# MouseGoggles_EyeTrack_Hat-1-1.net
KiCad netlist of a schematic drawn in EAGLE
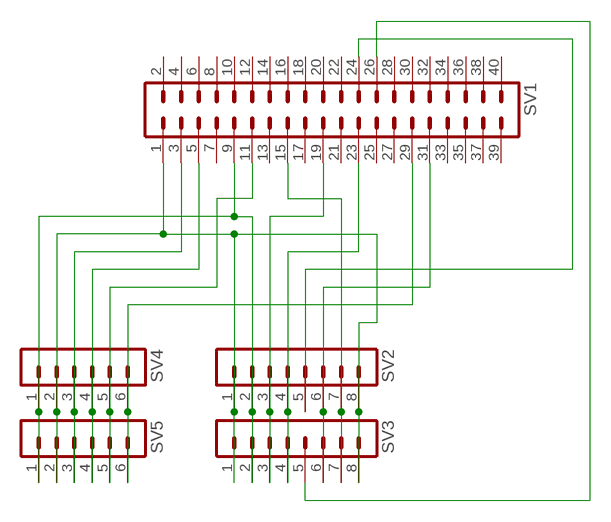
[diagram p0: schematic, sheet 1]

(export (version "E")
  (design (tool "Eeschema 10.0.6"))
  (components
    (comp (ref "SV1")
      (value "MA20-2")
      (footprint "eagle-import:MA20-2")
      (libsource (lib "eagle-import") (part "MA20-2"))
    )
    (comp (ref "SV2")
      (value "MA08-1")
      (footprint "eagle-import:MA08-1")
      (libsource (lib "eagle-import") (part "MA08-1"))
    )
    (comp (ref "SV3")
      (value "MA08-1")
      (footprint "eagle-import:MA08-1")
      (libsource (lib "eagle-import") (part "MA08-1"))
    )
    (comp (ref "SV4")
      (value "MA06-1")
      (footprint "eagle-import:MA06-1")
      (libsource (lib "eagle-import") (part "MA06-1"))
    )
    (comp (ref "SV5")
      (value "MA06-1")
      (footprint "eagle-import:MA06-1")
      (libsource (lib "eagle-import") (part "MA06-1"))
    )
  )
  (nets
    (net (code "1") (name "Net-(SV1-Pad1)") (class "Default")
      (node (ref "SV1") (pin "1") (pinfunction "1_1") (pintype "passive"))
      (node (ref "SV2") (pin "1") (pinfunction "1_1") (pintype "passive"))
      (node (ref "SV2") (pin "8") (pinfunction "8_8") (pintype "passive"))
      (node (ref "SV3") (pin "1") (pinfunction "1_1") (pintype "passive"))
      (node (ref "SV3") (pin "8") (pinfunction "8_8") (pintype "passive"))
      (node (ref "SV4") (pin "2") (pinfunction "2_2") (pintype "passive"))
      (node (ref "SV5") (pin "2") (pinfunction "2_2") (pintype "passive"))
    )
    (net (code "2") (name "Net-(SV1-Pad3)") (class "Default")
      (node (ref "SV1") (pin "3") (pinfunction "3_3") (pintype "passive"))
      (node (ref "SV4") (pin "3") (pinfunction "3_3") (pintype "passive"))
      (node (ref "SV5") (pin "3") (pinfunction "3_3") (pintype "passive"))
    )
    (net (code "3") (name "Net-(SV1-Pad5)") (class "Default")
      (node (ref "SV1") (pin "5") (pinfunction "5_5") (pintype "passive"))
      (node (ref "SV4") (pin "4") (pinfunction "4_4") (pintype "passive"))
      (node (ref "SV5") (pin "4") (pinfunction "4_4") (pintype "passive"))
    )
    (net (code "4") (name "Net-(SV1-Pad9)") (class "Default")
      (node (ref "SV1") (pin "9") (pinfunction "9_9") (pintype "passive"))
      (node (ref "SV2") (pin "2") (pinfunction "2_2") (pintype "passive"))
      (node (ref "SV3") (pin "2") (pinfunction "2_2") (pintype "passive"))
      (node (ref "SV4") (pin "1") (pinfunction "1_1") (pintype "passive"))
      (node (ref "SV5") (pin "1") (pinfunction "1_1") (pintype "passive"))
    )
    (net (code "5") (name "Net-(SV1-Pad11)") (class "Default")
      (node (ref "SV1") (pin "11") (pinfunction "11_11") (pintype "passive"))
      (node (ref "SV4") (pin "5") (pinfunction "5_5") (pintype "passive"))
      (node (ref "SV5") (pin "5") (pinfunction "5_5") (pintype "passive"))
    )
    (net (code "6") (name "Net-(SV1-Pad15)") (class "Default")
      (node (ref "SV1") (pin "15") (pinfunction "15_15") (pintype "passive"))
      (node (ref "SV2") (pin "7") (pinfunction "7_7") (pintype "passive"))
      (node (ref "SV3") (pin "7") (pinfunction "7_7") (pintype "passive"))
    )
    (net (code "7") (name "Net-(SV1-Pad19)") (class "Default")
      (node (ref "SV1") (pin "19") (pinfunction "19_19") (pintype "passive"))
      (node (ref "SV2") (pin "3") (pinfunction "3_3") (pintype "passive"))
      (node (ref "SV3") (pin "3") (pinfunction "3_3") (pintype "passive"))
    )
    (net (code "8") (name "Net-(SV1-Pad23)") (class "Default")
      (node (ref "SV1") (pin "23") (pinfunction "23_23") (pintype "passive"))
      (node (ref "SV2") (pin "4") (pinfunction "4_4") (pintype "passive"))
      (node (ref "SV3") (pin "4") (pinfunction "4_4") (pintype "passive"))
    )
    (net (code "9") (name "Net-(SV1-Pad24)") (class "Default")
      (node (ref "SV1") (pin "24") (pinfunction "24_24") (pintype "passive"))
      (node (ref "SV2") (pin "5") (pinfunction "5_5") (pintype "passive"))
    )
    (net (code "10") (name "Net-(SV1-Pad26)") (class "Default")
      (node (ref "SV1") (pin "26") (pinfunction "26_26") (pintype "passive"))
      (node (ref "SV3") (pin "5") (pinfunction "5_5") (pintype "passive"))
    )
    (net (code "11") (name "Net-(SV1-Pad29)") (class "Default")
      (node (ref "SV1") (pin "29") (pinfunction "29_29") (pintype "passive"))
      (node (ref "SV4") (pin "6") (pinfunction "6_6") (pintype "passive"))
      (node (ref "SV5") (pin "6") (pinfunction "6_6") (pintype "passive"))
    )
    (net (code "12") (name "Net-(SV1-Pad31)") (class "Default")
      (node (ref "SV1") (pin "31") (pinfunction "31_31") (pintype "passive"))
      (node (ref "SV2") (pin "6") (pinfunction "6_6") (pintype "passive"))
      (node (ref "SV3") (pin "6") (pinfunction "6_6") (pintype "passive"))
    )
    (net (code "13") (name "unconnected-(SV1-Pad2)") (class "Default")
      (node (ref "SV1") (pin "2") (pinfunction "2_2") (pintype "passive"))
    )
    (net (code "14") (name "unconnected-(SV1-Pad4)") (class "Default")
      (node (ref "SV1") (pin "4") (pinfunction "4_4") (pintype "passive"))
    )
    (net (code "15") (name "unconnected-(SV1-Pad6)") (class "Default")
      (node (ref "SV1") (pin "6") (pinfunction "6_6") (pintype "passive"))
    )
    (net (code "16") (name "unconnected-(SV1-Pad7)") (class "Default")
      (node (ref "SV1") (pin "7") (pinfunction "7_7") (pintype "passive"))
    )
    (net (code "17") (name "unconnected-(SV1-Pad8)") (class "Default")
      (node (ref "SV1") (pin "8") (pinfunction "8_8") (pintype "passive"))
    )
    (net (code "18") (name "unconnected-(SV1-Pad10)") (class "Default")
      (node (ref "SV1") (pin "10") (pinfunction "10_10") (pintype "passive"))
    )
    (net (code "19") (name "unconnected-(SV1-Pad12)") (class "Default")
      (node (ref "SV1") (pin "12") (pinfunction "12_12") (pintype "passive"))
    )
    (net (code "20") (name "unconnected-(SV1-Pad13)") (class "Default")
      (node (ref "SV1") (pin "13") (pinfunction "13_13") (pintype "passive"))
    )
    (net (code "21") (name "unconnected-(SV1-Pad14)") (class "Default")
      (node (ref "SV1") (pin "14") (pinfunction "14_14") (pintype "passive"))
    )
    (net (code "22") (name "unconnected-(SV1-Pad16)") (class "Default")
      (node (ref "SV1") (pin "16") (pinfunction "16_16") (pintype "passive"))
    )
    (net (code "23") (name "unconnected-(SV1-Pad17)") (class "Default")
      (node (ref "SV1") (pin "17") (pinfunction "17_17") (pintype "passive"))
    )
    (net (code "24") (name "unconnected-(SV1-Pad18)") (class "Default")
      (node (ref "SV1") (pin "18") (pinfunction "18_18") (pintype "passive"))
    )
    (net (code "25") (name "unconnected-(SV1-Pad20)") (class "Default")
      (node (ref "SV1") (pin "20") (pinfunction "20_20") (pintype "passive"))
    )
    (net (code "26") (name "unconnected-(SV1-Pad21)") (class "Default")
      (node (ref "SV1") (pin "21") (pinfunction "21_21") (pintype "passive"))
    )
    (net (code "27") (name "unconnected-(SV1-Pad22)") (class "Default")
      (node (ref "SV1") (pin "22") (pinfunction "22_22") (pintype "passive"))
    )
    (net (code "28") (name "unconnected-(SV1-Pad25)") (class "Default")
      (node (ref "SV1") (pin "25") (pinfunction "25_25") (pintype "passive"))
    )
    (net (code "29") (name "unconnected-(SV1-Pad27)") (class "Default")
      (node (ref "SV1") (pin "27") (pinfunction "27_27") (pintype "passive"))
    )
    (net (code "30") (name "unconnected-(SV1-Pad28)") (class "Default")
      (node (ref "SV1") (pin "28") (pinfunction "28_28") (pintype "passive"))
    )
    (net (code "31") (name "unconnected-(SV1-Pad30)") (class "Default")
      (node (ref "SV1") (pin "30") (pinfunction "30_30") (pintype "passive"))
    )
    (net (code "32") (name "unconnected-(SV1-Pad32)") (class "Default")
      (node (ref "SV1") (pin "32") (pinfunction "32_32") (pintype "passive"))
    )
    (net (code "33") (name "unconnected-(SV1-Pad33)") (class "Default")
      (node (ref "SV1") (pin "33") (pinfunction "33_33") (pintype "passive"))
    )
    (net (code "34") (name "unconnected-(SV1-Pad34)") (class "Default")
      (node (ref "SV1") (pin "34") (pinfunction "34_34") (pintype "passive"))
    )
    (net (code "35") (name "unconnected-(SV1-Pad35)") (class "Default")
      (node (ref "SV1") (pin "35") (pinfunction "35_35") (pintype "passive"))
    )
    (net (code "36") (name "unconnected-(SV1-Pad36)") (class "Default")
      (node (ref "SV1") (pin "36") (pinfunction "36_36") (pintype "passive"))
    )
    (net (code "37") (name "unconnected-(SV1-Pad37)") (class "Default")
      (node (ref "SV1") (pin "37") (pinfunction "37_37") (pintype "passive"))
    )
    (net (code "38") (name "unconnected-(SV1-Pad38)") (class "Default")
      (node (ref "SV1") (pin "38") (pinfunction "38_38") (pintype "passive"))
    )
    (net (code "39") (name "unconnected-(SV1-Pad39)") (class "Default")
      (node (ref "SV1") (pin "39") (pinfunction "39_39") (pintype "passive"))
    )
    (net (code "40") (name "unconnected-(SV1-Pad40)") (class "Default")
      (node (ref "SV1") (pin "40") (pinfunction "40_40") (pintype "passive"))
    )
  )
)
